# DRIVERS_CONNECTORS.net
KiCad netlist of a schematic drawn in Altium Designer
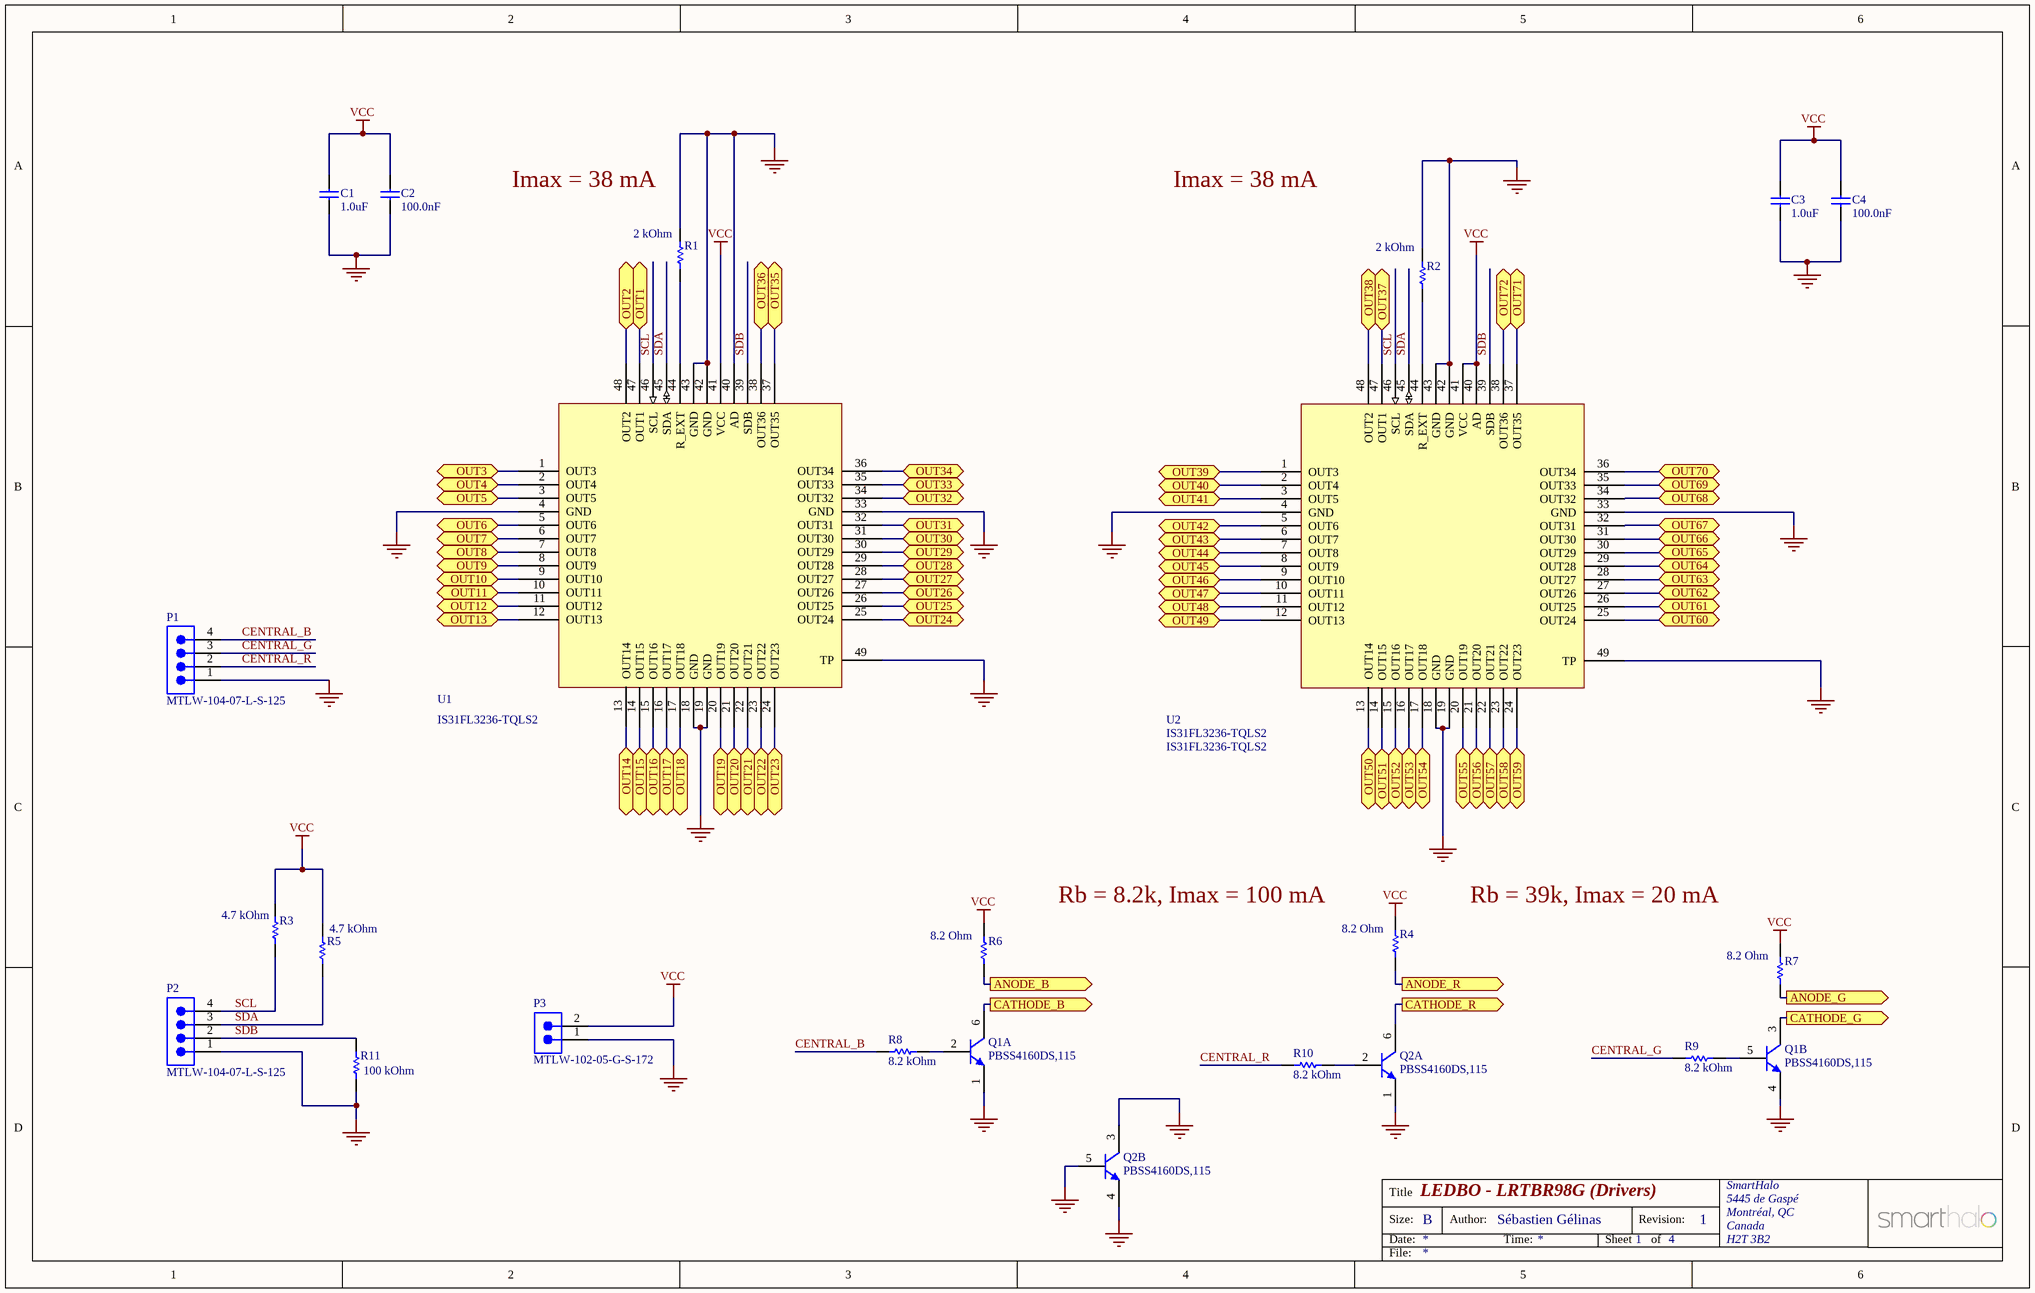
[diagram p0: DRIVERS_CONNECTORS.SchDoc]

(export (version "E")
  (design (tool "Eeschema 10.0.6"))
  (components
    (comp (ref "C1")
      (value "1.0uF")
      (footprint "CAPC0603(1608)100_N")
      (description "Chip Cap 0603 X7R 10%")
      (fields (field (name "PART NUMBER") "C0402-1n0") (field (name "PUBLISHER") "Nordic Semiconductor"))
      (libsource (lib "SmartHalo") (part "CAP0603"))
    )
    (comp (ref "C2")
      (value "100.0nF")
      (footprint "CAPC0603(1608)100_N")
      (description "Chip Cap 0603 X7R 10%")
      (fields (field (name "PART NUMBER") "C0402-1n0") (field (name "PUBLISHER") "Nordic Semiconductor"))
      (libsource (lib "SmartHalo") (part "CAP0603"))
    )
    (comp (ref "C3")
      (value "1.0uF")
      (footprint "CAPC0603(1608)100_N")
      (description "Chip Cap 0603 X7R 10%")
      (fields (field (name "PART NUMBER") "C0402-1n0") (field (name "PUBLISHER") "Nordic Semiconductor"))
      (libsource (lib "SmartHalo") (part "CAP0603"))
    )
    (comp (ref "C4")
      (value "100.0nF")
      (footprint "CAPC0603(1608)100_N")
      (description "Chip Cap 0603 X7R 10%")
      (fields (field (name "PART NUMBER") "C0402-1n0") (field (name "PUBLISHER") "Nordic Semiconductor"))
      (libsource (lib "SmartHalo") (part "CAP0603"))
    )
    (comp (ref "P1")
      (value "MTLW-104-07-L-S-125")
      (footprint "SMTC-MTLW-104-07-X-S-125")
      (fields (field (name "MANUFACTURER") "Samtec"))
      (libsource (lib "Altium Content Vault") (part "CMP-1024-00072-1"))
    )
    (comp (ref "P2")
      (value "MTLW-104-07-L-S-125")
      (footprint "SMTC-MTLW-104-07-X-S-125")
      (fields (field (name "MANUFACTURER") "Samtec"))
      (libsource (lib "Altium Content Vault") (part "CMP-1024-00072-1"))
    )
    (comp (ref "P3")
      (value "MTLW-102-05-G-S-172")
      (footprint "SMTC-MTLW-102-05-X-S-172")
      (fields (field (name "MANUFACTURER") "Samtec"))
      (libsource (lib "Altium Content Vault") (part "CMP-1024-00064-1"))
    )
    (comp (ref "Q1")
      (value "PBSS4160DS,115")
      (footprint "NXP-SC74_M")
      (description "TRANS 2NPN 60V 1A 6TSOP")
      (fields (field (name "PARTNUMBER") "PBSS4160DS") (field (name "MANUFACTURER") "NXP Semiconductors"))
      (libsource (lib "SmartHalo") (part "PBSS4160DS,115"))
    )
    (comp (ref "Q2")
      (value "PBSS4160DS,115")
      (footprint "NXP-SC74_M")
      (description "TRANS 2NPN 60V 1A 6TSOP")
      (fields (field (name "PARTNUMBER") "PBSS4160DS") (field (name "MANUFACTURER") "NXP Semiconductors"))
      (libsource (lib "SmartHalo") (part "PBSS4160DS,115"))
    )
    (comp (ref "R1")
      (value "2 kOhm")
      (footprint "RESC0603(1608)_N")
      (description "2k 0.1W 5% 0603 (1608 Metric)  SMD")
      (fields (field (name "TOLERANCE") "5 %") (field (name "POWER") "0.1 W"))
      (libsource (lib "Altium Content Vault") (part "CMP-1012-00090-1"))
    )
    (comp (ref "R2")
      (value "2 kOhm")
      (footprint "RESC0603(1608)_N")
      (description "2k 0.1W 5% 0603 (1608 Metric)  SMD")
      (fields (field (name "TOLERANCE") "5 %") (field (name "POWER") "0.1 W"))
      (libsource (lib "Altium Content Vault") (part "CMP-1012-00090-1"))
    )
    (comp (ref "R3")
      (value "4.7 kOhm")
      (footprint "RESC0603(1608)_N")
      (description "4K7 0.1W 5% 0603 (1608 Metric)  SMD")
      (fields (field (name "TOLERANCE") "5 %") (field (name "POWER") "0.1 W"))
      (libsource (lib "Altium Content Vault") (part "CMP-1012-00090-1"))
    )
    (comp (ref "R4")
      (value "8.2 Ohm")
      (footprint "RESC0603(1608)_N")
      (description "8R2 0.1W 5% 0603 (1608 Metric)  SMD")
      (fields (field (name "TOLERANCE") "5 %") (field (name "POWER") "0.1 W"))
      (libsource (lib "Altium Content Vault") (part "CMP-1012-00090-1"))
    )
    (comp (ref "R5")
      (value "4.7 kOhm")
      (footprint "RESC0603(1608)_N")
      (description "4K7 0.1W 5% 0603 (1608 Metric)  SMD")
      (fields (field (name "TOLERANCE") "5 %") (field (name "POWER") "0.1 W"))
      (libsource (lib "Altium Content Vault") (part "CMP-1012-00090-1"))
    )
    (comp (ref "R6")
      (value "8.2 Ohm")
      (footprint "RESC0603(1608)_N")
      (description "8R2 0.1W 5% 0603 (1608 Metric)  SMD")
      (fields (field (name "TOLERANCE") "5 %") (field (name "POWER") "0.1 W"))
      (libsource (lib "Altium Content Vault") (part "CMP-1012-00090-1"))
    )
    (comp (ref "R7")
      (value "8.2 Ohm")
      (footprint "RESC0603(1608)_N")
      (description "8R2 0.1W 5% 0603 (1608 Metric)  SMD")
      (fields (field (name "TOLERANCE") "5 %") (field (name "POWER") "0.1 W"))
      (libsource (lib "Altium Content Vault") (part "CMP-1012-00090-1"))
    )
    (comp (ref "R8")
      (value "8.2 kOhm")
      (footprint "RESC0603(1608)_N")
      (description "8K2 0.1W 5% 0603 (1608 Metric)  SMD")
      (fields (field (name "TOLERANCE") "5 %") (field (name "POWER") "0.1 W"))
      (libsource (lib "Altium Content Vault") (part "CMP-1012-00090-1"))
    )
    (comp (ref "R9")
      (value "8.2 kOhm")
      (footprint "RESC0603(1608)_N")
      (description "8K2 0.1W 5% 0603 (1608 Metric)  SMD")
      (fields (field (name "TOLERANCE") "5 %") (field (name "POWER") "0.1 W"))
      (libsource (lib "Altium Content Vault") (part "CMP-1012-00090-1"))
    )
    (comp (ref "R10")
      (value "8.2 kOhm")
      (footprint "RESC0603(1608)_N")
      (description "8K2 0.1W 5% 0603 (1608 Metric)  SMD")
      (fields (field (name "TOLERANCE") "5 %") (field (name "POWER") "0.1 W"))
      (libsource (lib "Altium Content Vault") (part "CMP-1012-00090-1"))
    )
    (comp (ref "R11")
      (value "100 kOhm")
      (footprint "RESC0603(1608)_N")
      (description "100k 0.1W 5% 0603 (1608 Metric)  SMD")
      (fields (field (name "TOLERANCE") "5 %") (field (name "POWER") "0.1 W"))
      (libsource (lib "Altium Content Vault") (part "CMP-1012-00090-1"))
    )
    (comp (ref "U1")
      (value "IS31FL3236-TQLS2")
      (footprint "TQFP48")
      (description "IC 36 CHANNELS LED DRIVER")
      (fields (field (name "MANUFACTURER") "ISSI"))
      (libsource (lib "SmartHalo") (part "IS31FL3236-TQLS2"))
    )
    (comp (ref "U2")
      (value "IS31FL3236-TQLS2")
      (footprint "TQFP48")
      (description "IC 36 CHANNELS LED DRIVER")
      (fields
        (field (name "MANUFACTURER") "ISSI")
        (field (name "MANUFACTURER PART NUMBER") "IS31FL3236-TQLS2")
      )
      (libsource (lib "SmartHalo") (part "IS31FL3236-TQLS2"))
    )
  )
  (nets
    (net (code "1") (name "/ANODE_B") (class "Default")
      (node (ref "R6") (pin "1") (pinfunction "1_1") (pintype "passive"))
    )
    (net (code "2") (name "/ANODE_G") (class "Default")
      (node (ref "R7") (pin "1") (pinfunction "1_1") (pintype "passive"))
    )
    (net (code "3") (name "/ANODE_R") (class "Default")
      (node (ref "R4") (pin "1") (pinfunction "1_1") (pintype "passive"))
    )
    (net (code "4") (name "/CATHODE_B") (class "Default")
      (node (ref "Q1") (pin "6") (pinfunction "C1_6") (pintype "passive"))
    )
    (net (code "5") (name "/CATHODE_G") (class "Default")
      (node (ref "Q1") (pin "3") (pinfunction "C2_3") (pintype "passive"))
    )
    (net (code "6") (name "/CATHODE_R") (class "Default")
      (node (ref "Q2") (pin "6") (pinfunction "C1_6") (pintype "passive"))
    )
    (net (code "7") (name "/CENTRAL_B") (class "Default")
      (node (ref "P1") (pin "4") (pinfunction "4_4") (pintype "passive"))
      (node (ref "R8") (pin "2") (pinfunction "2_2") (pintype "passive"))
    )
    (net (code "8") (name "/CENTRAL_G") (class "Default")
      (node (ref "P1") (pin "3") (pinfunction "3_3") (pintype "passive"))
      (node (ref "R9") (pin "2") (pinfunction "2_2") (pintype "passive"))
    )
    (net (code "9") (name "/CENTRAL_R") (class "Default")
      (node (ref "P1") (pin "2") (pinfunction "2_2") (pintype "passive"))
      (node (ref "R10") (pin "2") (pinfunction "2_2") (pintype "passive"))
    )
    (net (code "10") (name "/OUT1") (class "Default")
      (node (ref "U1") (pin "47") (pinfunction "OUT1_47") (pintype "passive"))
    )
    (net (code "11") (name "/OUT2") (class "Default")
      (node (ref "U1") (pin "48") (pinfunction "OUT2_48") (pintype "passive"))
    )
    (net (code "12") (name "/OUT3") (class "Default")
      (node (ref "U1") (pin "1") (pinfunction "OUT3_1") (pintype "passive"))
    )
    (net (code "13") (name "/OUT4") (class "Default")
      (node (ref "U1") (pin "2") (pinfunction "OUT4_2") (pintype "passive"))
    )
    (net (code "14") (name "/OUT5") (class "Default")
      (node (ref "U1") (pin "3") (pinfunction "OUT5_3") (pintype "passive"))
    )
    (net (code "15") (name "/OUT6") (class "Default")
      (node (ref "U1") (pin "5") (pinfunction "OUT6_5") (pintype "passive"))
    )
    (net (code "16") (name "/OUT7") (class "Default")
      (node (ref "U1") (pin "6") (pinfunction "OUT7_6") (pintype "passive"))
    )
    (net (code "17") (name "/OUT8") (class "Default")
      (node (ref "U1") (pin "7") (pinfunction "OUT8_7") (pintype "passive"))
    )
    (net (code "18") (name "/OUT9") (class "Default")
      (node (ref "U1") (pin "8") (pinfunction "OUT9_8") (pintype "passive"))
    )
    (net (code "19") (name "/OUT10") (class "Default")
      (node (ref "U1") (pin "9") (pinfunction "OUT10_9") (pintype "passive"))
    )
    (net (code "20") (name "/OUT11") (class "Default")
      (node (ref "U1") (pin "10") (pinfunction "OUT11_10") (pintype "passive"))
    )
    (net (code "21") (name "/OUT12") (class "Default")
      (node (ref "U1") (pin "11") (pinfunction "OUT12_11") (pintype "passive"))
    )
    (net (code "22") (name "/OUT13") (class "Default")
      (node (ref "U1") (pin "12") (pinfunction "OUT13_12") (pintype "passive"))
    )
    (net (code "23") (name "/OUT14") (class "Default")
      (node (ref "U1") (pin "13") (pinfunction "OUT14_13") (pintype "passive"))
    )
    (net (code "24") (name "/OUT15") (class "Default")
      (node (ref "U1") (pin "14") (pinfunction "OUT15_14") (pintype "passive"))
    )
    (net (code "25") (name "/OUT16") (class "Default")
      (node (ref "U1") (pin "15") (pinfunction "OUT16_15") (pintype "passive"))
    )
    (net (code "26") (name "/OUT17") (class "Default")
      (node (ref "U1") (pin "16") (pinfunction "OUT17_16") (pintype "passive"))
    )
    (net (code "27") (name "/OUT18") (class "Default")
      (node (ref "U1") (pin "17") (pinfunction "OUT18_17") (pintype "passive"))
    )
    (net (code "28") (name "/OUT19") (class "Default")
      (node (ref "U1") (pin "20") (pinfunction "OUT19_20") (pintype "passive"))
    )
    (net (code "29") (name "/OUT20") (class "Default")
      (node (ref "U1") (pin "21") (pinfunction "OUT20_21") (pintype "passive"))
    )
    (net (code "30") (name "/OUT21") (class "Default")
      (node (ref "U1") (pin "22") (pinfunction "OUT21_22") (pintype "passive"))
    )
    (net (code "31") (name "/OUT22") (class "Default")
      (node (ref "U1") (pin "23") (pinfunction "OUT22_23") (pintype "passive"))
    )
    (net (code "32") (name "/OUT23") (class "Default")
      (node (ref "U1") (pin "24") (pinfunction "OUT23_24") (pintype "passive"))
    )
    (net (code "33") (name "/OUT24") (class "Default")
      (node (ref "U1") (pin "25") (pinfunction "OUT24_25") (pintype "passive"))
    )
    (net (code "34") (name "/OUT25") (class "Default")
      (node (ref "U1") (pin "26") (pinfunction "OUT25_26") (pintype "passive"))
    )
    (net (code "35") (name "/OUT26") (class "Default")
      (node (ref "U1") (pin "27") (pinfunction "OUT26_27") (pintype "passive"))
    )
    (net (code "36") (name "/OUT27") (class "Default")
      (node (ref "U1") (pin "28") (pinfunction "OUT27_28") (pintype "passive"))
    )
    (net (code "37") (name "/OUT28") (class "Default")
      (node (ref "U1") (pin "29") (pinfunction "OUT28_29") (pintype "passive"))
    )
    (net (code "38") (name "/OUT29") (class "Default")
      (node (ref "U1") (pin "30") (pinfunction "OUT29_30") (pintype "passive"))
    )
    (net (code "39") (name "/OUT30") (class "Default")
      (node (ref "U1") (pin "31") (pinfunction "OUT30_31") (pintype "passive"))
    )
    (net (code "40") (name "/OUT31") (class "Default")
      (node (ref "U1") (pin "32") (pinfunction "OUT31_32") (pintype "passive"))
    )
    (net (code "41") (name "/OUT32") (class "Default")
      (node (ref "U1") (pin "34") (pinfunction "OUT32_34") (pintype "passive"))
    )
    (net (code "42") (name "/OUT33") (class "Default")
      (node (ref "U1") (pin "35") (pinfunction "OUT33_35") (pintype "passive"))
    )
    (net (code "43") (name "/OUT34") (class "Default")
      (node (ref "U1") (pin "36") (pinfunction "OUT34_36") (pintype "passive"))
    )
    (net (code "44") (name "/OUT35") (class "Default")
      (node (ref "U1") (pin "37") (pinfunction "OUT35_37") (pintype "passive"))
    )
    (net (code "45") (name "/OUT36") (class "Default")
      (node (ref "U1") (pin "38") (pinfunction "OUT36_38") (pintype "passive"))
    )
    (net (code "46") (name "/OUT37") (class "Default")
      (node (ref "U2") (pin "47") (pinfunction "OUT1_47") (pintype "passive"))
    )
    (net (code "47") (name "/OUT38") (class "Default")
      (node (ref "U2") (pin "48") (pinfunction "OUT2_48") (pintype "passive"))
    )
    (net (code "48") (name "/OUT39") (class "Default")
      (node (ref "U2") (pin "1") (pinfunction "OUT3_1") (pintype "passive"))
    )
    (net (code "49") (name "/OUT40") (class "Default")
      (node (ref "U2") (pin "2") (pinfunction "OUT4_2") (pintype "passive"))
    )
    (net (code "50") (name "/OUT41") (class "Default")
      (node (ref "U2") (pin "3") (pinfunction "OUT5_3") (pintype "passive"))
    )
    (net (code "51") (name "/OUT42") (class "Default")
      (node (ref "U2") (pin "5") (pinfunction "OUT6_5") (pintype "passive"))
    )
    (net (code "52") (name "/OUT43") (class "Default")
      (node (ref "U2") (pin "6") (pinfunction "OUT7_6") (pintype "passive"))
    )
    (net (code "53") (name "/OUT44") (class "Default")
      (node (ref "U2") (pin "7") (pinfunction "OUT8_7") (pintype "passive"))
    )
    (net (code "54") (name "/OUT45") (class "Default")
      (node (ref "U2") (pin "8") (pinfunction "OUT9_8") (pintype "passive"))
    )
    (net (code "55") (name "/OUT46") (class "Default")
      (node (ref "U2") (pin "9") (pinfunction "OUT10_9") (pintype "passive"))
    )
    (net (code "56") (name "/OUT47") (class "Default")
      (node (ref "U2") (pin "10") (pinfunction "OUT11_10") (pintype "passive"))
    )
    (net (code "57") (name "/OUT48") (class "Default")
      (node (ref "U2") (pin "11") (pinfunction "OUT12_11") (pintype "passive"))
    )
    (net (code "58") (name "/OUT49") (class "Default")
      (node (ref "U2") (pin "12") (pinfunction "OUT13_12") (pintype "passive"))
    )
    (net (code "59") (name "/OUT50") (class "Default")
      (node (ref "U2") (pin "13") (pinfunction "OUT14_13") (pintype "passive"))
    )
    (net (code "60") (name "/OUT51") (class "Default")
      (node (ref "U2") (pin "14") (pinfunction "OUT15_14") (pintype "passive"))
    )
    (net (code "61") (name "/OUT52") (class "Default")
      (node (ref "U2") (pin "15") (pinfunction "OUT16_15") (pintype "passive"))
    )
    (net (code "62") (name "/OUT53") (class "Default")
      (node (ref "U2") (pin "16") (pinfunction "OUT17_16") (pintype "passive"))
    )
    (net (code "63") (name "/OUT54") (class "Default")
      (node (ref "U2") (pin "17") (pinfunction "OUT18_17") (pintype "passive"))
    )
    (net (code "64") (name "/OUT55") (class "Default")
      (node (ref "U2") (pin "20") (pinfunction "OUT19_20") (pintype "passive"))
    )
    (net (code "65") (name "/OUT56") (class "Default")
      (node (ref "U2") (pin "21") (pinfunction "OUT20_21") (pintype "passive"))
    )
    (net (code "66") (name "/OUT57") (class "Default")
      (node (ref "U2") (pin "22") (pinfunction "OUT21_22") (pintype "passive"))
    )
    (net (code "67") (name "/OUT58") (class "Default")
      (node (ref "U2") (pin "23") (pinfunction "OUT22_23") (pintype "passive"))
    )
    (net (code "68") (name "/OUT59") (class "Default")
      (node (ref "U2") (pin "24") (pinfunction "OUT23_24") (pintype "passive"))
    )
    (net (code "69") (name "/OUT60") (class "Default")
      (node (ref "U2") (pin "25") (pinfunction "OUT24_25") (pintype "passive"))
    )
    (net (code "70") (name "/OUT61") (class "Default")
      (node (ref "U2") (pin "26") (pinfunction "OUT25_26") (pintype "passive"))
    )
    (net (code "71") (name "/OUT62") (class "Default")
      (node (ref "U2") (pin "27") (pinfunction "OUT26_27") (pintype "passive"))
    )
    (net (code "72") (name "/OUT63") (class "Default")
      (node (ref "U2") (pin "28") (pinfunction "OUT27_28") (pintype "passive"))
    )
    (net (code "73") (name "/OUT64") (class "Default")
      (node (ref "U2") (pin "29") (pinfunction "OUT28_29") (pintype "passive"))
    )
    (net (code "74") (name "/OUT65") (class "Default")
      (node (ref "U2") (pin "30") (pinfunction "OUT29_30") (pintype "passive"))
    )
    (net (code "75") (name "/OUT66") (class "Default")
      (node (ref "U2") (pin "31") (pinfunction "OUT30_31") (pintype "passive"))
    )
    (net (code "76") (name "/OUT67") (class "Default")
      (node (ref "U2") (pin "32") (pinfunction "OUT31_32") (pintype "passive"))
    )
    (net (code "77") (name "/OUT68") (class "Default")
      (node (ref "U2") (pin "34") (pinfunction "OUT32_34") (pintype "passive"))
    )
    (net (code "78") (name "/OUT69") (class "Default")
      (node (ref "U2") (pin "35") (pinfunction "OUT33_35") (pintype "passive"))
    )
    (net (code "79") (name "/OUT70") (class "Default")
      (node (ref "U2") (pin "36") (pinfunction "OUT34_36") (pintype "passive"))
    )
    (net (code "80") (name "/OUT71") (class "Default")
      (node (ref "U2") (pin "37") (pinfunction "OUT35_37") (pintype "passive"))
    )
    (net (code "81") (name "/OUT72") (class "Default")
      (node (ref "U2") (pin "38") (pinfunction "OUT36_38") (pintype "passive"))
    )
    (net (code "82") (name "/SCL") (class "Default")
      (node (ref "P2") (pin "4") (pinfunction "4_4") (pintype "passive"))
      (node (ref "R3") (pin "1") (pinfunction "1_1") (pintype "passive"))
      (node (ref "U1") (pin "46") (pinfunction "SCL_46") (pintype "input"))
      (node (ref "U2") (pin "46") (pinfunction "SCL_46") (pintype "input"))
    )
    (net (code "83") (name "/SDA") (class "Default")
      (node (ref "P2") (pin "3") (pinfunction "3_3") (pintype "passive"))
      (node (ref "R5") (pin "1") (pinfunction "1_1") (pintype "passive"))
      (node (ref "U1") (pin "45") (pinfunction "SDA_45") (pintype "bidirectional"))
      (node (ref "U2") (pin "45") (pinfunction "SDA_45") (pintype "bidirectional"))
    )
    (net (code "84") (name "/SDB") (class "Default")
      (node (ref "P2") (pin "2") (pinfunction "2_2") (pintype "passive"))
      (node (ref "R11") (pin "2") (pinfunction "2_2") (pintype "passive"))
      (node (ref "U1") (pin "39") (pinfunction "SDB_39") (pintype "passive"))
      (node (ref "U2") (pin "39") (pinfunction "SDB_39") (pintype "passive"))
    )
    (net (code "85") (name "GND") (class "Default")
      (node (ref "C1") (pin "2") (pinfunction "2_2") (pintype "passive"))
      (node (ref "C2") (pin "2") (pinfunction "2_2") (pintype "passive"))
      (node (ref "C3") (pin "2") (pinfunction "2_2") (pintype "passive"))
      (node (ref "C4") (pin "2") (pinfunction "2_2") (pintype "passive"))
      (node (ref "P1") (pin "1") (pinfunction "1_1") (pintype "passive"))
      (node (ref "P2") (pin "1") (pinfunction "1_1") (pintype "passive"))
      (node (ref "P3") (pin "1") (pinfunction "1_1") (pintype "passive"))
      (node (ref "Q1") (pin "1") (pinfunction "E1_1") (pintype "passive"))
      (node (ref "Q1") (pin "4") (pinfunction "E2_4") (pintype "passive"))
      (node (ref "Q2") (pin "1") (pinfunction "E1_1") (pintype "passive"))
      (node (ref "Q2") (pin "3") (pinfunction "C2_3") (pintype "passive"))
      (node (ref "Q2") (pin "4") (pinfunction "E2_4") (pintype "passive"))
      (node (ref "Q2") (pin "5") (pinfunction "B2_5") (pintype "passive"))
      (node (ref "R1") (pin "2") (pinfunction "2_2") (pintype "passive"))
      (node (ref "R11") (pin "1") (pinfunction "1_1") (pintype "passive"))
      (node (ref "R2") (pin "2") (pinfunction "2_2") (pintype "passive"))
      (node (ref "U1") (pin "18") (pinfunction "GND_18") (pintype "power_in"))
      (node (ref "U1") (pin "19") (pinfunction "GND_19") (pintype "power_in"))
      (node (ref "U1") (pin "33") (pinfunction "GND_33") (pintype "power_in"))
      (node (ref "U1") (pin "4") (pinfunction "GND_4") (pintype "power_in"))
      (node (ref "U1") (pin "40") (pinfunction "AD_40") (pintype "passive"))
      (node (ref "U1") (pin "42") (pinfunction "GND_42") (pintype "power_in"))
      (node (ref "U1") (pin "43") (pinfunction "GND_43") (pintype "power_in"))
      (node (ref "U1") (pin "49") (pinfunction "TP_49") (pintype "power_in"))
      (node (ref "U2") (pin "18") (pinfunction "GND_18") (pintype "power_in"))
      (node (ref "U2") (pin "19") (pinfunction "GND_19") (pintype "power_in"))
      (node (ref "U2") (pin "33") (pinfunction "GND_33") (pintype "power_in"))
      (node (ref "U2") (pin "4") (pinfunction "GND_4") (pintype "power_in"))
      (node (ref "U2") (pin "42") (pinfunction "GND_42") (pintype "power_in"))
      (node (ref "U2") (pin "43") (pinfunction "GND_43") (pintype "power_in"))
      (node (ref "U2") (pin "49") (pinfunction "TP_49") (pintype "power_in"))
    )
    (net (code "86") (name "Net-(Q1A-B1)") (class "Default")
      (node (ref "Q1") (pin "2") (pinfunction "B1_2") (pintype "passive"))
      (node (ref "R8") (pin "1") (pinfunction "1_1") (pintype "passive"))
    )
    (net (code "87") (name "Net-(Q1B-B2)") (class "Default")
      (node (ref "Q1") (pin "5") (pinfunction "B2_5") (pintype "passive"))
      (node (ref "R9") (pin "1") (pinfunction "1_1") (pintype "passive"))
    )
    (net (code "88") (name "Net-(Q2A-B1)") (class "Default")
      (node (ref "Q2") (pin "2") (pinfunction "B1_2") (pintype "passive"))
      (node (ref "R10") (pin "1") (pinfunction "1_1") (pintype "passive"))
    )
    (net (code "89") (name "Net-(U1-R_EXT)") (class "Default")
      (node (ref "R1") (pin "1") (pinfunction "1_1") (pintype "passive"))
      (node (ref "U1") (pin "44") (pinfunction "R_EXT_44") (pintype "passive"))
    )
    (net (code "90") (name "Net-(U2-R_EXT)") (class "Default")
      (node (ref "R2") (pin "1") (pinfunction "1_1") (pintype "passive"))
      (node (ref "U2") (pin "44") (pinfunction "R_EXT_44") (pintype "passive"))
    )
    (net (code "91") (name "VCC") (class "Default")
      (node (ref "C1") (pin "1") (pinfunction "1_1") (pintype "passive"))
      (node (ref "C2") (pin "1") (pinfunction "1_1") (pintype "passive"))
      (node (ref "C3") (pin "1") (pinfunction "1_1") (pintype "passive"))
      (node (ref "C4") (pin "1") (pinfunction "1_1") (pintype "passive"))
      (node (ref "P3") (pin "2") (pinfunction "2_2") (pintype "passive"))
      (node (ref "R3") (pin "2") (pinfunction "2_2") (pintype "passive"))
      (node (ref "R4") (pin "2") (pinfunction "2_2") (pintype "passive"))
      (node (ref "R5") (pin "2") (pinfunction "2_2") (pintype "passive"))
      (node (ref "R6") (pin "2") (pinfunction "2_2") (pintype "passive"))
      (node (ref "R7") (pin "2") (pinfunction "2_2") (pintype "passive"))
      (node (ref "U1") (pin "41") (pinfunction "VCC_41") (pintype "power_in"))
      (node (ref "U2") (pin "40") (pinfunction "AD_40") (pintype "passive"))
      (node (ref "U2") (pin "41") (pinfunction "VCC_41") (pintype "power_in"))
    )
  )
)
